# Schematic.net
KiCad netlist of a schematic drawn in EAGLE
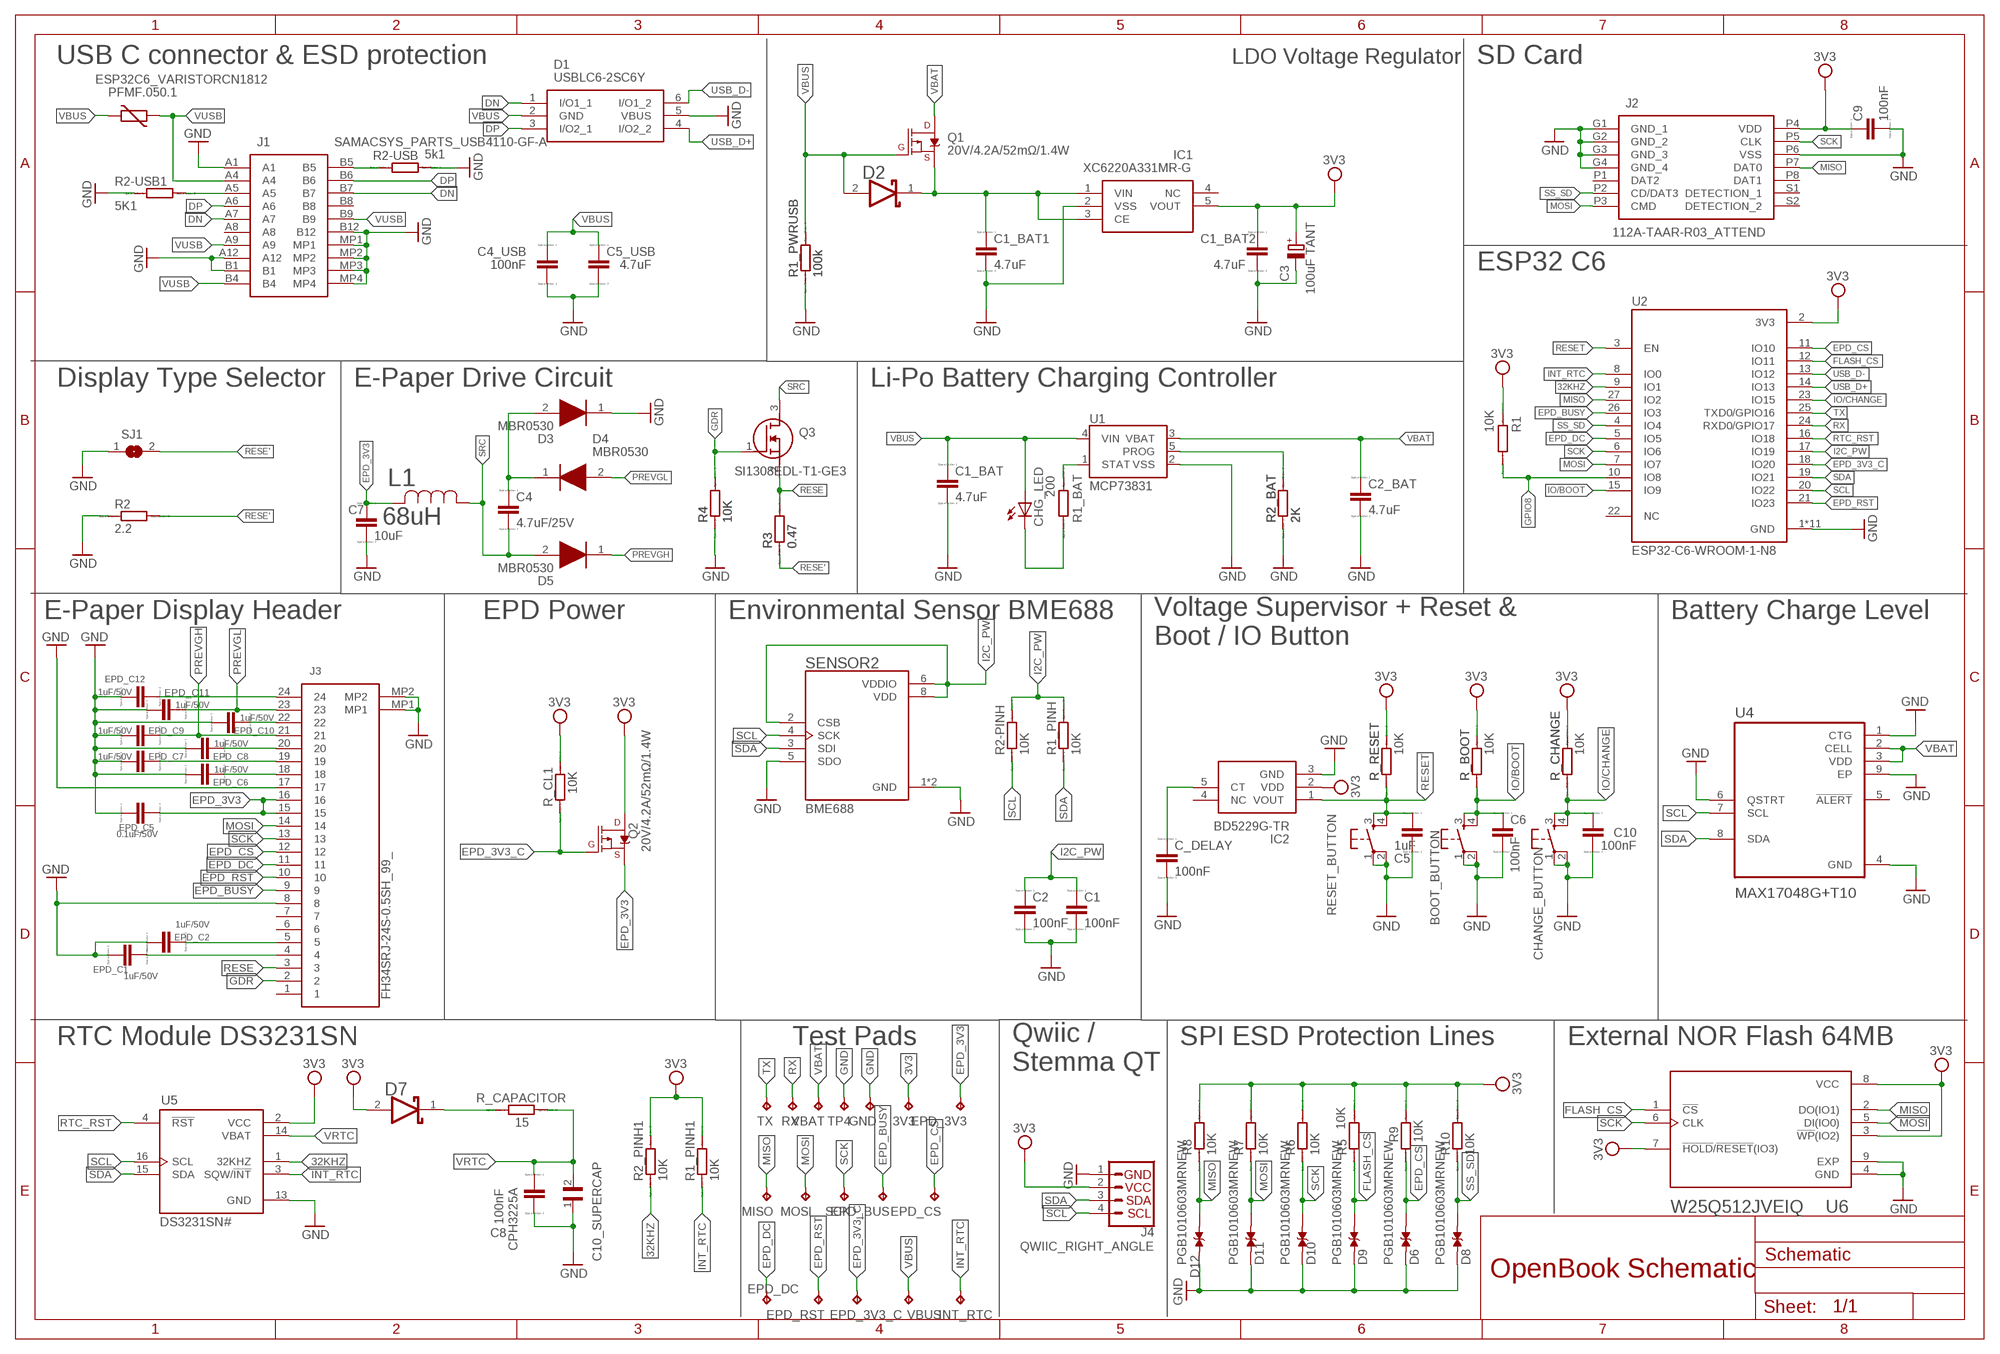
[diagram p0: schematic, sheet 1]

(export (version "E")
  (design (tool "Eeschema 10.0.6"))
  (components
    (comp (ref "3V3")
      (value "TP")
      (footprint "eagle-import:TP20R")
      (libsource (lib "eagle-import") (part "TP"))
    )
    (comp (ref "BOOT_BUTTON")
      (value "BUTTON_CUSYOMV1NEW")
      (footprint "eagle-import:MYBUTTON")
      (libsource (lib "eagle-import") (part "BUTTON_CUSYOMV1NEW"))
    )
    (comp (ref "C1")
      (value "100nF")
      (footprint "eagle-import:ESP32_WROVER_EAGLE-LTSPICE_C0402")
      (libsource (lib "eagle-import") (part "ESP32_WROVER_EAGLE-LTSPICE_C"))
    )
    (comp (ref "C1_BAT")
      (value "4.7uF")
      (footprint "eagle-import:ESP32_WROVER_EAGLE-LTSPICE_C0402")
      (libsource (lib "eagle-import") (part "ESP32_WROVER_EAGLE-LTSPICE_C"))
    )
    (comp (ref "C1_BAT1")
      (value "4.7uF")
      (footprint "eagle-import:ESP32_WROVER_EAGLE-LTSPICE_C0402")
      (libsource (lib "eagle-import") (part "ESP32_WROVER_EAGLE-LTSPICE_C"))
    )
    (comp (ref "C1_BAT2")
      (value "4.7uF")
      (footprint "eagle-import:ESP32_WROVER_EAGLE-LTSPICE_C0402")
      (libsource (lib "eagle-import") (part "ESP32_WROVER_EAGLE-LTSPICE_C"))
    )
    (comp (ref "C2")
      (value "100nF")
      (footprint "eagle-import:ESP32_WROVER_EAGLE-LTSPICE_C0402")
      (libsource (lib "eagle-import") (part "ESP32_WROVER_EAGLE-LTSPICE_C"))
    )
    (comp (ref "C2_BAT")
      (value "4.7uF")
      (footprint "eagle-import:ESP32_WROVER_EAGLE-LTSPICE_C0402")
      (libsource (lib "eagle-import") (part "ESP32_WROVER_EAGLE-LTSPICE_C"))
    )
    (comp (ref "C3")
      (value "100uF TANT")
      (footprint "eagle-import:RCL_CT3528")
      (libsource (lib "eagle-import") (part "RCL_CPOL-EUCT3528"))
    )
    (comp (ref "C4")
      (value "4.7uF/25V")
      (footprint "eagle-import:ESP32_WROVER_EAGLE-LTSPICE_C0402")
      (libsource (lib "eagle-import") (part "ESP32_WROVER_EAGLE-LTSPICE_C"))
    )
    (comp (ref "C4_USB")
      (value "100nF")
      (footprint "eagle-import:ESP32_WROVER_EAGLE-LTSPICE_C0402")
      (libsource (lib "eagle-import") (part "ESP32_WROVER_EAGLE-LTSPICE_C"))
    )
    (comp (ref "C5")
      (value "1uF")
      (footprint "eagle-import:ESP32_WROVER_EAGLE-LTSPICE_C0402")
      (libsource (lib "eagle-import") (part "ESP32_WROVER_EAGLE-LTSPICE_C"))
    )
    (comp (ref "C5_USB")
      (value "4.7uF")
      (footprint "eagle-import:ESP32_WROVER_EAGLE-LTSPICE_C0402")
      (libsource (lib "eagle-import") (part "ESP32_WROVER_EAGLE-LTSPICE_C"))
    )
    (comp (ref "C6")
      (value "100nF")
      (footprint "eagle-import:ESP32_WROVER_EAGLE-LTSPICE_C0402")
      (libsource (lib "eagle-import") (part "ESP32_WROVER_EAGLE-LTSPICE_C"))
    )
    (comp (ref "C7")
      (value "10uF")
      (footprint "eagle-import:ESP32_WROVER_EAGLE-LTSPICE_C0402")
      (libsource (lib "eagle-import") (part "ESP32_WROVER_EAGLE-LTSPICE_C"))
    )
    (comp (ref "C8")
      (value "100nF")
      (footprint "eagle-import:ESP32_WROVER_EAGLE-LTSPICE_C0402")
      (libsource (lib "eagle-import") (part "ESP32_WROVER_EAGLE-LTSPICE_C"))
    )
    (comp (ref "C9")
      (value "100nF")
      (footprint "eagle-import:ESP32_WROVER_EAGLE-LTSPICE_C0402")
      (libsource (lib "eagle-import") (part "ESP32_WROVER_EAGLE-LTSPICE_C"))
    )
    (comp (ref "C10")
      (value "100nF")
      (footprint "eagle-import:ESP32_WROVER_EAGLE-LTSPICE_C0402")
      (libsource (lib "eagle-import") (part "ESP32_WROVER_EAGLE-LTSPICE_C"))
    )
    (comp (ref "C10_SUPERCAP")
      (value "CPH3225A")
      (footprint "eagle-import:CAPCP3225X100N")
      (fields (field (name "MF") "Seiko Instruments"))
      (libsource (lib "eagle-import") (part "CPH3225A"))
    )
    (comp (ref "CHANGE_BUTTON")
      (value "BUTTON_CUSYOMV1NEW")
      (footprint "eagle-import:MYBUTTON")
      (libsource (lib "eagle-import") (part "BUTTON_CUSYOMV1NEW"))
    )
    (comp (ref "CHG_LED")
      (value "ADAFRUIT_LEDCHIP-LED0603")
      (footprint "eagle-import:ADAFRUIT_CHIP-LED0603")
      (libsource (lib "eagle-import") (part "ADAFRUIT_LEDCHIP-LED0603"))
    )
    (comp (ref "C_DELAY")
      (value "100nF")
      (footprint "eagle-import:ESP32_WROVER_EAGLE-LTSPICE_C0402")
      (libsource (lib "eagle-import") (part "ESP32_WROVER_EAGLE-LTSPICE_C"))
    )
    (comp (ref "D1")
      (value "USBLC6-2SC6Y")
      (footprint "eagle-import:SOT95P280X145-6N")
      (fields (field (name "MF") "STMicroelectronics"))
      (libsource (lib "eagle-import") (part "USBLC6-2SC6Y"))
    )
    (comp (ref "D2")
      (value "ESP32_WROVER_AVX---SD0805S020S1R0_AVX_SD0805S020S1R0_0_0AVX_SD0805S020S1R0_0_0")
      (footprint "eagle-import:ESP32_WROVER_AVX---SD0805S020S1R0_AVX_SD0805S020S1R0_0")
      (fields
        (field (name "DIGIKEY_PART_NUMBER") "478-7800-1-ND")
        (field (name "MF") "AVX")
        (field (name "MOUSER_PART_NUMBER") "581-SD0805S020S1R0")
      )
      (libsource (lib "eagle-import") (part "ESP32_WROVER_AVX---SD0805S020S1R0_AVX_SD0805S020S1R0_0_0AVX_SD0805S020S1R0_0_0"))
    )
    (comp (ref "D3")
      (value "MBR0530")
      (footprint "eagle-import:SOD3716X135N")
      (fields (field (name "MF") "ON Semiconductor"))
      (libsource (lib "eagle-import") (part "MBR0530"))
    )
    (comp (ref "D4")
      (value "MBR0530")
      (footprint "eagle-import:SOD3716X135N")
      (fields (field (name "MF") "ON Semiconductor"))
      (libsource (lib "eagle-import") (part "MBR0530"))
    )
    (comp (ref "D5")
      (value "MBR0530")
      (footprint "eagle-import:SOD3716X135N")
      (fields (field (name "MF") "ON Semiconductor"))
      (libsource (lib "eagle-import") (part "MBR0530"))
    )
    (comp (ref "D6")
      (value "PGB1010603MRNEW")
      (footprint "eagle-import:DIOC1608X36N")
      (libsource (lib "eagle-import") (part "PGB1010603MRNEW"))
    )
    (comp (ref "D7")
      (value "ESP32_WROVER_AVX---SD0805S020S1R0_AVX_SD0805S020S1R0_0_0AVX_SD0805S020S1R0_0_0")
      (footprint "eagle-import:ESP32_WROVER_AVX---SD0805S020S1R0_AVX_SD0805S020S1R0_0")
      (fields
        (field (name "DIGIKEY_PART_NUMBER") "478-7800-1-ND")
        (field (name "MF") "AVX")
        (field (name "MOUSER_PART_NUMBER") "581-SD0805S020S1R0")
      )
      (libsource (lib "eagle-import") (part "ESP32_WROVER_AVX---SD0805S020S1R0_AVX_SD0805S020S1R0_0_0AVX_SD0805S020S1R0_0_0"))
    )
    (comp (ref "D8")
      (value "PGB1010603MRNEW")
      (footprint "eagle-import:DIOC1608X36N")
      (libsource (lib "eagle-import") (part "PGB1010603MRNEW"))
    )
    (comp (ref "D9")
      (value "PGB1010603MRNEW")
      (footprint "eagle-import:DIOC1608X36N")
      (libsource (lib "eagle-import") (part "PGB1010603MRNEW"))
    )
    (comp (ref "D10")
      (value "PGB1010603MRNEW")
      (footprint "eagle-import:DIOC1608X36N")
      (libsource (lib "eagle-import") (part "PGB1010603MRNEW"))
    )
    (comp (ref "D11")
      (value "PGB1010603MRNEW")
      (footprint "eagle-import:DIOC1608X36N")
      (libsource (lib "eagle-import") (part "PGB1010603MRNEW"))
    )
    (comp (ref "D12")
      (value "PGB1010603MRNEW")
      (footprint "eagle-import:DIOC1608X36N")
      (libsource (lib "eagle-import") (part "PGB1010603MRNEW"))
    )
    (comp (ref "EPD_3V3")
      (value "TP")
      (footprint "eagle-import:TP20R")
      (libsource (lib "eagle-import") (part "TP"))
    )
    (comp (ref "EPD_3V3_C")
      (value "TP")
      (footprint "eagle-import:TP20R")
      (libsource (lib "eagle-import") (part "TP"))
    )
    (comp (ref "EPD_BUS")
      (value "TP")
      (footprint "eagle-import:TP20R")
      (libsource (lib "eagle-import") (part "TP"))
    )
    (comp (ref "EPD_C1")
      (value "1uF/50V")
      (footprint "eagle-import:ESP32_WROVER_EAGLE-LTSPICE_C0402")
      (libsource (lib "eagle-import") (part "ESP32_WROVER_EAGLE-LTSPICE_C"))
    )
    (comp (ref "EPD_C2")
      (value "1uF/50V")
      (footprint "eagle-import:ESP32_WROVER_EAGLE-LTSPICE_C0402")
      (libsource (lib "eagle-import") (part "ESP32_WROVER_EAGLE-LTSPICE_C"))
    )
    (comp (ref "EPD_C5")
      (value "0.1uF/50V")
      (footprint "eagle-import:ESP32_WROVER_EAGLE-LTSPICE_C0402")
      (libsource (lib "eagle-import") (part "ESP32_WROVER_EAGLE-LTSPICE_C"))
    )
    (comp (ref "EPD_C6")
      (value "1uF/50V")
      (footprint "eagle-import:ESP32_WROVER_EAGLE-LTSPICE_C0402")
      (libsource (lib "eagle-import") (part "ESP32_WROVER_EAGLE-LTSPICE_C"))
    )
    (comp (ref "EPD_C7")
      (value "1uF/50V")
      (footprint "eagle-import:ESP32_WROVER_EAGLE-LTSPICE_C0402")
      (libsource (lib "eagle-import") (part "ESP32_WROVER_EAGLE-LTSPICE_C"))
    )
    (comp (ref "EPD_C8")
      (value "1uF/50V")
      (footprint "eagle-import:ESP32_WROVER_EAGLE-LTSPICE_C0402")
      (libsource (lib "eagle-import") (part "ESP32_WROVER_EAGLE-LTSPICE_C"))
    )
    (comp (ref "EPD_C9")
      (value "1uF/50V")
      (footprint "eagle-import:ESP32_WROVER_EAGLE-LTSPICE_C0402")
      (libsource (lib "eagle-import") (part "ESP32_WROVER_EAGLE-LTSPICE_C"))
    )
    (comp (ref "EPD_C10")
      (value "1uF/50V")
      (footprint "eagle-import:ESP32_WROVER_EAGLE-LTSPICE_C0402")
      (libsource (lib "eagle-import") (part "ESP32_WROVER_EAGLE-LTSPICE_C"))
    )
    (comp (ref "EPD_C11")
      (value "1uF/50V")
      (footprint "eagle-import:ESP32_WROVER_EAGLE-LTSPICE_C0402")
      (libsource (lib "eagle-import") (part "ESP32_WROVER_EAGLE-LTSPICE_C"))
    )
    (comp (ref "EPD_C12")
      (value "1uF/50V")
      (footprint "eagle-import:ESP32_WROVER_EAGLE-LTSPICE_C0402")
      (libsource (lib "eagle-import") (part "ESP32_WROVER_EAGLE-LTSPICE_C"))
    )
    (comp (ref "EPD_CS")
      (value "TP")
      (footprint "eagle-import:TP20R")
      (libsource (lib "eagle-import") (part "TP"))
    )
    (comp (ref "EPD_DC")
      (value "TP")
      (footprint "eagle-import:TP20R")
      (libsource (lib "eagle-import") (part "TP"))
    )
    (comp (ref "EPD_RST")
      (value "TP")
      (footprint "eagle-import:TP20R")
      (libsource (lib "eagle-import") (part "TP"))
    )
    (comp (ref "GND")
      (value "TP")
      (footprint "eagle-import:TP20R")
      (libsource (lib "eagle-import") (part "TP"))
    )
    (comp (ref "IC1")
      (value "XC6220A331MR-G")
      (footprint "eagle-import:SOT95P280X120-5N")
      (fields (field (name "MOUSER_PART_NUMBER") "865-XC6220A331MR-G"))
      (libsource (lib "eagle-import") (part "XC6220A331MR-G"))
    )
    (comp (ref "IC2")
      (value "BD5229G-TR")
      (footprint "eagle-import:SOT95P280X125-5N")
      (fields (field (name "MOUSER_PART_NUMBER") "755-BD5229G-TR"))
      (libsource (lib "eagle-import") (part "BD5229G-TR"))
    )
    (comp (ref "INT_RTC")
      (value "TP")
      (footprint "eagle-import:TP20R")
      (libsource (lib "eagle-import") (part "TP"))
    )
    (comp (ref "J1")
      (value "SAMACSYS_PARTS_USB4110-GF-A")
      (footprint "eagle-import:SAMACSYS_PARTS_USB4110GFA")
      (fields
        (field (name "MANUFACTURER_PART_NUMBER") "USB4110-GF-A")
        (field (name "MOUSER_PART_NUMBER") "640-USB4110-GF-A")
      )
      (libsource (lib "eagle-import") (part "SAMACSYS_PARTS_USB4110-GF-A"))
    )
    (comp (ref "J2")
      (value "112A-TAAR-R03_ATTEND")
      (footprint "eagle-import:112ATAARR03ATTEND")
      (fields (field (name "MANUFACTURER_PART_NUMBER") "112A-TAAR-R03 ATTEND"))
      (libsource (lib "eagle-import") (part "112A-TAAR-R03_ATTEND"))
    )
    (comp (ref "J3")
      (value "FH34SRJ-24S-0.5SH_99_")
      (footprint "eagle-import:FH34SRJ24S05SH99")
      (fields
        (field (name "MANUFACTURER_PART_NUMBER") "FH34SRJ-24S-0.5SH(99)")
        (field (name "MOUSER_PART_NUMBER") "798-FH34SRJ24S05SH99")
      )
      (libsource (lib "eagle-import") (part "FH34SRJ-24S-0.5SH_99_"))
    )
    (comp (ref "J4")
      (value "QWIIC_RIGHT_ANGLE")
      (footprint "eagle-import:JST04_1MM_RA")
      (libsource (lib "eagle-import") (part "QWIIC_CONNECTORJS-1MM"))
    )
    (comp (ref "L1")
      (value "68uH")
      (footprint "eagle-import:IND_4828-WE-TPC_WRE")
      (fields
        (field (name "MANUFACTURER_PART_NUMBER") "744043680")
        (field (name "COPYRIGHT") "Copyright (C) 2024 Ultra Librarian. All rights reserved.")
      )
      (libsource (lib "eagle-import") (part "744043680IND_4828-WE-TPC_WRE"))
    )
    (comp (ref "MISO")
      (value "TP")
      (footprint "eagle-import:TP20R")
      (libsource (lib "eagle-import") (part "TP"))
    )
    (comp (ref "MOSI")
      (value "TP")
      (footprint "eagle-import:TP20R")
      (libsource (lib "eagle-import") (part "TP"))
    )
    (comp (ref "PFMF.050.1")
      (value "ESP32C6_VARISTORCN1812")
      (footprint "eagle-import:ESP32C6_VARISTOR_CT_CN1812")
      (libsource (lib "eagle-import") (part "ESP32C6_VARISTORCN1812"))
    )
    (comp (ref "Q1")
      (value "20V/4.2A/52mΩ/1.4W")
      (footprint "eagle-import:ESP32_WROVER_SPARKFUN-DISCRETESEMI_SOT23-3")
      (libsource (lib "eagle-import") (part "ESP32_WROVER_SPARKFUN-DISCRETESEMI_MOSFET_PCH-DMG2305UX-7"))
    )
    (comp (ref "Q2")
      (value "20V/4.2A/52mΩ/1.4W")
      (footprint "eagle-import:ESP32_WROVER_SPARKFUN-DISCRETESEMI_SOT23-3")
      (libsource (lib "eagle-import") (part "ESP32_WROVER_SPARKFUN-DISCRETESEMI_MOSFET_PCH-DMG2305UX-7"))
    )
    (comp (ref "Q3")
      (value "SI1308EDL-T1-GE3")
      (footprint "eagle-import:SOT65P210X110-3N")
      (fields (field (name "MF") "Vishay Siliconix"))
      (libsource (lib "eagle-import") (part "SI1308EDL-T1-GE3"))
    )
    (comp (ref "R1")
      (value "10K")
      (footprint "eagle-import:ESP32_WROVER_EAGLE-LTSPICE_R0402")
      (libsource (lib "eagle-import") (part "ESP32_WROVER_EAGLE-LTSPICE_R"))
    )
    (comp (ref "R1_BAT")
      (value "200")
      (footprint "eagle-import:ESP32_WROVER_EAGLE-LTSPICE_R0402")
      (libsource (lib "eagle-import") (part "ESP32_WROVER_EAGLE-LTSPICE_R"))
    )
    (comp (ref "R1_PINH")
      (value "10K")
      (footprint "eagle-import:ESP32_WROVER_EAGLE-LTSPICE_R0402")
      (libsource (lib "eagle-import") (part "ESP32_WROVER_EAGLE-LTSPICE_R"))
    )
    (comp (ref "R1_PINH1")
      (value "10K")
      (footprint "eagle-import:ESP32_WROVER_EAGLE-LTSPICE_R0402")
      (libsource (lib "eagle-import") (part "ESP32_WROVER_EAGLE-LTSPICE_R"))
    )
    (comp (ref "R1_PWRUSB")
      (value "100k")
      (footprint "eagle-import:ESP32_WROVER_EAGLE-LTSPICE_R0402")
      (libsource (lib "eagle-import") (part "ESP32_WROVER_EAGLE-LTSPICE_R"))
    )
    (comp (ref "R2")
      (value "2.2")
      (footprint "eagle-import:ESP32_WROVER_EAGLE-LTSPICE_R0402")
      (libsource (lib "eagle-import") (part "ESP32_WROVER_EAGLE-LTSPICE_R"))
    )
    (comp (ref "R2-PINH")
      (value "10K")
      (footprint "eagle-import:ESP32_WROVER_EAGLE-LTSPICE_R0402")
      (libsource (lib "eagle-import") (part "ESP32_WROVER_EAGLE-LTSPICE_R"))
    )
    (comp (ref "R2-USB")
      (value "5k1")
      (footprint "eagle-import:ESP32_WROVER_EAGLE-LTSPICE_R0402")
      (libsource (lib "eagle-import") (part "ESP32_WROVER_EAGLE-LTSPICE_R"))
    )
    (comp (ref "R2-USB1")
      (value "5K1")
      (footprint "eagle-import:ESP32_WROVER_EAGLE-LTSPICE_R0402")
      (libsource (lib "eagle-import") (part "ESP32_WROVER_EAGLE-LTSPICE_R"))
    )
    (comp (ref "R2_BAT")
      (value "2K")
      (footprint "eagle-import:ESP32_WROVER_EAGLE-LTSPICE_R0402")
      (libsource (lib "eagle-import") (part "ESP32_WROVER_EAGLE-LTSPICE_R"))
    )
    (comp (ref "R2_PINH1")
      (value "10K")
      (footprint "eagle-import:ESP32_WROVER_EAGLE-LTSPICE_R0402")
      (libsource (lib "eagle-import") (part "ESP32_WROVER_EAGLE-LTSPICE_R"))
    )
    (comp (ref "R3")
      (value "0.47")
      (footprint "eagle-import:ESP32_WROVER_EAGLE-LTSPICE_R0402")
      (libsource (lib "eagle-import") (part "ESP32_WROVER_EAGLE-LTSPICE_R"))
    )
    (comp (ref "R4")
      (value "10K")
      (footprint "eagle-import:ESP32_WROVER_EAGLE-LTSPICE_R0402")
      (libsource (lib "eagle-import") (part "ESP32_WROVER_EAGLE-LTSPICE_R"))
    )
    (comp (ref "R5")
      (value "10K")
      (footprint "eagle-import:ESP32_WROVER_EAGLE-LTSPICE_R0402")
      (libsource (lib "eagle-import") (part "ESP32_WROVER_EAGLE-LTSPICE_R"))
    )
    (comp (ref "R6")
      (value "10K")
      (footprint "eagle-import:ESP32_WROVER_EAGLE-LTSPICE_R0402")
      (libsource (lib "eagle-import") (part "ESP32_WROVER_EAGLE-LTSPICE_R"))
    )
    (comp (ref "R7")
      (value "10K")
      (footprint "eagle-import:ESP32_WROVER_EAGLE-LTSPICE_R0402")
      (libsource (lib "eagle-import") (part "ESP32_WROVER_EAGLE-LTSPICE_R"))
    )
    (comp (ref "R8")
      (value "10K")
      (footprint "eagle-import:ESP32_WROVER_EAGLE-LTSPICE_R0402")
      (libsource (lib "eagle-import") (part "ESP32_WROVER_EAGLE-LTSPICE_R"))
    )
    (comp (ref "R9")
      (value "10K")
      (footprint "eagle-import:ESP32_WROVER_EAGLE-LTSPICE_R0402")
      (libsource (lib "eagle-import") (part "ESP32_WROVER_EAGLE-LTSPICE_R"))
    )
    (comp (ref "R10")
      (value "10K")
      (footprint "eagle-import:ESP32_WROVER_EAGLE-LTSPICE_R0402")
      (libsource (lib "eagle-import") (part "ESP32_WROVER_EAGLE-LTSPICE_R"))
    )
    (comp (ref "RESET_BUTTON")
      (value "BUTTON_CUSYOMV1NEW")
      (footprint "eagle-import:MYBUTTON")
      (libsource (lib "eagle-import") (part "BUTTON_CUSYOMV1NEW"))
    )
    (comp (ref "RX")
      (value "TP")
      (footprint "eagle-import:TP20R")
      (libsource (lib "eagle-import") (part "TP"))
    )
    (comp (ref "R_BOOT")
      (value "10K")
      (footprint "eagle-import:ESP32_WROVER_EAGLE-LTSPICE_R0402")
      (libsource (lib "eagle-import") (part "ESP32_WROVER_EAGLE-LTSPICE_R"))
    )
    (comp (ref "R_CAPACITOR")
      (value "15")
      (footprint "eagle-import:ESP32_WROVER_EAGLE-LTSPICE_R0402")
      (libsource (lib "eagle-import") (part "ESP32_WROVER_EAGLE-LTSPICE_R"))
    )
    (comp (ref "R_CHANGE")
      (value "10K")
      (footprint "eagle-import:ESP32_WROVER_EAGLE-LTSPICE_R0402")
      (libsource (lib "eagle-import") (part "ESP32_WROVER_EAGLE-LTSPICE_R"))
    )
    (comp (ref "R_CL1")
      (value "10K")
      (footprint "eagle-import:ESP32_WROVER_EAGLE-LTSPICE_R0402")
      (libsource (lib "eagle-import") (part "ESP32_WROVER_EAGLE-LTSPICE_R"))
    )
    (comp (ref "R_RESET")
      (value "10K")
      (footprint "eagle-import:ESP32_WROVER_EAGLE-LTSPICE_R0402")
      (libsource (lib "eagle-import") (part "ESP32_WROVER_EAGLE-LTSPICE_R"))
    )
    (comp (ref "SCK")
      (value "TP")
      (footprint "eagle-import:TP20R")
      (libsource (lib "eagle-import") (part "TP"))
    )
    (comp (ref "SENSOR2")
      (value "ESP32_WROVER_BME680_BME680")
      (footprint "eagle-import:ESP32_WROVER_BME680_PSON80P300X300X100-8N")
      (fields (field (name "MF") "Bosch Sensortec") (field (name "MP") "BME680"))
      (libsource (lib "eagle-import") (part "ESP32_WROVER_BME680_BME680"))
    )
    (comp (ref "SJ1") (value "SJ") (footprint "eagle-import:SJ") (libsource (lib "eagle-import") (part "SJ")))
    (comp (ref "TP4")
      (value "TP")
      (footprint "eagle-import:TP20R")
      (libsource (lib "eagle-import") (part "TP"))
    )
    (comp (ref "TX")
      (value "TP")
      (footprint "eagle-import:TP20R")
      (libsource (lib "eagle-import") (part "TP"))
    )
    (comp (ref "U1")
      (value "ESP32_WROVER_SPARKFUN-IC-POWER_MCP73831")
      (footprint "eagle-import:ESP32_WROVER_SPARKFUN-IC-POWER_SOT23-5")
      (libsource (lib "eagle-import") (part "ESP32_WROVER_SPARKFUN-IC-POWER_MCP73831"))
    )
    (comp (ref "U2")
      (value "ESP32-C6-WROOM-1-N8")
      (footprint "eagle-import:XCVR_ESP32-C6-WROOM-1-N8")
      (fields (field (name "MF") "Espressif Systems"))
      (libsource (lib "eagle-import") (part "ESP32-C6-WROOM-1-N8"))
    )
    (comp (ref "U4")
      (value "MAX17048G+T10")
      (footprint "eagle-import:SON50P200X200X80-9N")
      (fields (field (name "MF") "Analog Devices"))
      (libsource (lib "eagle-import") (part "MAX17048G+T10"))
    )
    (comp (ref "U5")
      (value "DS3231SN#")
      (footprint "eagle-import:SOIC127P1032X265-16N")
      (fields (field (name "MF") "Analog Devices"))
      (libsource (lib "eagle-import") (part "DS3231SN#"))
    )
    (comp (ref "U6")
      (value "W25Q512JVEIQ")
      (footprint "eagle-import:SON127P600X800X80-9N")
      (fields (field (name "MF") "Winbond Electronics"))
      (libsource (lib "eagle-import") (part "W25Q512JVEIQ"))
    )
    (comp (ref "VBAT")
      (value "TP")
      (footprint "eagle-import:TP20R")
      (libsource (lib "eagle-import") (part "TP"))
    )
    (comp (ref "VBUS")
      (value "TP")
      (footprint "eagle-import:TP20R")
      (libsource (lib "eagle-import") (part "TP"))
    )
  )
  (nets
    (net (code "1") (name "3V3") (class "Default")
      (node (ref "3V3") (pin "TP") (pinfunction "TP_TP") (pintype "input"))
      (node (ref "C1_BAT2") (pin "1") (pinfunction "1_1") (pintype "passive"))
      (node (ref "C3") (pin "+") (pinfunction "+_+") (pintype "passive"))
      (node (ref "C9") (pin "1") (pinfunction "1_1") (pintype "passive"))
      (node (ref "D7") (pin "2") (pinfunction "ANODE_2") (pintype "bidirectional"))
      (node (ref "IC1") (pin "5") (pinfunction "VOUT_5") (pintype "bidirectional"))
      (node (ref "IC2") (pin "2") (pinfunction "VDD_2") (pintype "bidirectional"))
      (node (ref "J2") (pin "P4") (pinfunction "VDD_P4") (pintype "bidirectional"))
      (node (ref "J4") (pin "2") (pinfunction "2_2") (pintype "power_in"))
      (node (ref "Q2") (pin "3") (pinfunction "D_3") (pintype "bidirectional"))
      (node (ref "R1") (pin "2") (pinfunction "2_2") (pintype "passive"))
      (node (ref "R10") (pin "2") (pinfunction "2_2") (pintype "passive"))
      (node (ref "R1_PINH1") (pin "2") (pinfunction "2_2") (pintype "passive"))
      (node (ref "R2_PINH1") (pin "2") (pinfunction "2_2") (pintype "passive"))
      (node (ref "R5") (pin "2") (pinfunction "2_2") (pintype "passive"))
      (node (ref "R6") (pin "2") (pinfunction "2_2") (pintype "passive"))
      (node (ref "R7") (pin "2") (pinfunction "2_2") (pintype "passive"))
      (node (ref "R8") (pin "2") (pinfunction "2_2") (pintype "passive"))
      (node (ref "R9") (pin "2") (pinfunction "2_2") (pintype "passive"))
      (node (ref "R_BOOT") (pin "2") (pinfunction "2_2") (pintype "passive"))
      (node (ref "R_CHANGE") (pin "2") (pinfunction "2_2") (pintype "passive"))
      (node (ref "R_CL1") (pin "2") (pinfunction "2_2") (pintype "passive"))
      (node (ref "R_RESET") (pin "2") (pinfunction "2_2") (pintype "passive"))
      (node (ref "U2") (pin "2") (pinfunction "3V3_2") (pintype "power_in"))
      (node (ref "U5") (pin "2") (pinfunction "VCC_2") (pintype "power_in"))
      (node (ref "U6") (pin "3") (pinfunction "~{WP}(IO2)_3") (pintype "bidirectional"))
      (node (ref "U6") (pin "7") (pinfunction "~{HOLD}/~{RESET}(IO3)_7") (pintype "bidirectional"))
      (node (ref "U6") (pin "8") (pinfunction "VCC_8") (pintype "power_in"))
    )
    (net (code "2") (name "32KHZ") (class "Default")
      (node (ref "R2_PINH1") (pin "1") (pinfunction "1_1") (pintype "passive"))
      (node (ref "U2") (pin "9") (pinfunction "IO1_9") (pintype "bidirectional"))
      (node (ref "U5") (pin "1") (pinfunction "32KHZ_1") (pintype "output"))
    )
    (net (code "3") (name "DN") (class "Default")
      (node (ref "D1") (pin "1") (pinfunction "I/O1_1_1") (pintype "bidirectional"))
      (node (ref "J1") (pin "A7") (pinfunction "A7_A7") (pintype "bidirectional"))
      (node (ref "J1") (pin "B7") (pinfunction "B7_B7") (pintype "bidirectional"))
    )
    (net (code "4") (name "DP") (class "Default")
      (node (ref "D1") (pin "3") (pinfunction "I/O2_1_3") (pintype "bidirectional"))
      (node (ref "J1") (pin "A6") (pinfunction "A6_A6") (pintype "bidirectional"))
      (node (ref "J1") (pin "B6") (pinfunction "B6_B6") (pintype "bidirectional"))
    )
    (net (code "5") (name "EPD_3V3") (class "Default")
      (node (ref "C7") (pin "1") (pinfunction "1_1") (pintype "passive"))
      (node (ref "EPD_3V3") (pin "TP") (pinfunction "TP_TP") (pintype "input"))
      (node (ref "EPD_C5") (pin "2") (pinfunction "2_2") (pintype "passive"))
      (node (ref "J3") (pin "15") (pinfunction "15_15") (pintype "bidirectional"))
      (node (ref "J3") (pin "16") (pinfunction "16_16") (pintype "bidirectional"))
      (node (ref "L1") (pin "2") (pinfunction "2_2") (pintype "passive"))
      (node (ref "Q2") (pin "2") (pinfunction "S_2") (pintype "bidirectional"))
    )
    (net (code "6") (name "EPD_3V3_C") (class "Default")
      (node (ref "EPD_3V3_C") (pin "TP") (pinfunction "TP_TP") (pintype "input"))
      (node (ref "Q2") (pin "1") (pinfunction "G_1") (pintype "bidirectional"))
      (node (ref "R_CL1") (pin "1") (pinfunction "1_1") (pintype "passive"))
      (node (ref "U2") (pin "18") (pinfunction "IO20_18") (pintype "bidirectional"))
    )
    (net (code "7") (name "EPD_BUSY") (class "Default")
      (node (ref "EPD_BUS") (pin "TP") (pinfunction "TP_TP") (pintype "input"))
      (node (ref "J3") (pin "9") (pinfunction "9_9") (pintype "bidirectional"))
      (node (ref "U2") (pin "26") (pinfunction "IO3_26") (pintype "bidirectional"))
    )
    (net (code "8") (name "EPD_CS") (class "Default")
      (node (ref "D6") (pin "1") (pinfunction "2_1") (pintype "passive"))
      (node (ref "EPD_CS") (pin "TP") (pinfunction "TP_TP") (pintype "input"))
      (node (ref "J3") (pin "12") (pinfunction "12_12") (pintype "bidirectional"))
      (node (ref "R9") (pin "1") (pinfunction "1_1") (pintype "passive"))
      (node (ref "U2") (pin "11") (pinfunction "IO10_11") (pintype "bidirectional"))
    )
    (net (code "9") (name "EPD_DC") (class "Default")
      (node (ref "EPD_DC") (pin "TP") (pinfunction "TP_TP") (pintype "input"))
      (node (ref "J3") (pin "11") (pinfunction "11_11") (pintype "bidirectional"))
      (node (ref "U2") (pin "5") (pinfunction "IO5_5") (pintype "bidirectional"))
    )
    (net (code "10") (name "EPD_RST") (class "Default")
      (node (ref "EPD_RST") (pin "TP") (pinfunction "TP_TP") (pintype "input"))
      (node (ref "J3") (pin "10") (pinfunction "10_10") (pintype "bidirectional"))
      (node (ref "U2") (pin "21") (pinfunction "IO23_21") (pintype "bidirectional"))
    )
    (net (code "11") (name "FLASH_CS") (class "Default")
      (node (ref "D9") (pin "1") (pinfunction "2_1") (pintype "passive"))
      (node (ref "R5") (pin "1") (pinfunction "1_1") (pintype "passive"))
      (node (ref "U2") (pin "12") (pinfunction "IO11_12") (pintype "bidirectional"))
      (node (ref "U6") (pin "1") (pinfunction "~{CS}_1") (pintype "input"))
    )
    (net (code "12") (name "GDR") (class "Default")
      (node (ref "J3") (pin "2") (pinfunction "2_2") (pintype "bidirectional"))
      (node (ref "Q3") (pin "1") (pinfunction "G_1") (pintype "bidirectional"))
      (node (ref "R4") (pin "2") (pinfunction "2_2") (pintype "passive"))
    )
    (net (code "13") (name "GND") (class "Default")
      (node (ref "BOOT_BUTTON") (pin "1") (pinfunction "1_1") (pintype "passive"))
      (node (ref "BOOT_BUTTON") (pin "2") (pinfunction "2_2") (pintype "passive"))
      (node (ref "C1") (pin "2") (pinfunction "2_2") (pintype "passive"))
      (node (ref "C10") (pin "2") (pinfunction "2_2") (pintype "passive"))
      (node (ref "C10_SUPERCAP") (pin "1") (pinfunction "1_1") (pintype "passive"))
      (node (ref "C1_BAT") (pin "2") (pinfunction "2_2") (pintype "passive"))
      (node (ref "C1_BAT1") (pin "2") (pinfunction "2_2") (pintype "passive"))
      (node (ref "C1_BAT2") (pin "2") (pinfunction "2_2") (pintype "passive"))
      (node (ref "C2") (pin "2") (pinfunction "2_2") (pintype "passive"))
      (node (ref "C2_BAT") (pin "2") (pinfunction "2_2") (pintype "passive"))
      (node (ref "C3") (pin "-") (pinfunction "-_-") (pintype "passive"))
      (node (ref "C4_USB") (pin "2") (pinfunction "2_2") (pintype "passive"))
      (node (ref "C5") (pin "2") (pinfunction "2_2") (pintype "passive"))
      (node (ref "C5_USB") (pin "2") (pinfunction "2_2") (pintype "passive"))
      (node (ref "C6") (pin "2") (pinfunction "2_2") (pintype "passive"))
      (node (ref "C7") (pin "2") (pinfunction "2_2") (pintype "passive"))
      (node (ref "C8") (pin "2") (pinfunction "2_2") (pintype "passive"))
      (node (ref "C9") (pin "2") (pinfunction "2_2") (pintype "passive"))
      (node (ref "CHANGE_BUTTON") (pin "1") (pinfunction "1_1") (pintype "passive"))
      (node (ref "CHANGE_BUTTON") (pin "2") (pinfunction "2_2") (pintype "passive"))
      (node (ref "C_DELAY") (pin "2") (pinfunction "2_2") (pintype "passive"))
      (node (ref "D1") (pin "5") (pinfunction "VBUS_5") (pintype "bidirectional"))
      (node (ref "D10") (pin "2") (pinfunction "1_2") (pintype "passive"))
      (node (ref "D11") (pin "2") (pinfunction "1_2") (pintype "passive"))
      (node (ref "D12") (pin "2") (pinfunction "1_2") (pintype "passive"))
      (node (ref "D3") (pin "1") (pinfunction "K_1") (pintype "bidirectional"))
      (node (ref "D6") (pin "2") (pinfunction "1_2") (pintype "passive"))
      (node (ref "D8") (pin "2") (pinfunction "1_2") (pintype "passive"))
      (node (ref "D9") (pin "2") (pinfunction "1_2") (pintype "passive"))
      (node (ref "EPD_C1") (pin "1") (pinfunction "1_1") (pintype "passive"))
      (node (ref "EPD_C10") (pin "1") (pinfunction "1_1") (pintype "passive"))
      (node (ref "EPD_C11") (pin "1") (pinfunction "1_1") (pintype "passive"))
      (node (ref "EPD_C12") (pin "1") (pinfunction "1_1") (pintype "passive"))
      (node (ref "EPD_C2") (pin "1") (pinfunction "1_1") (pintype "passive"))
      (node (ref "EPD_C5") (pin "1") (pinfunction "1_1") (pintype "passive"))
      (node (ref "EPD_C6") (pin "1") (pinfunction "1_1") (pintype "passive"))
      (node (ref "EPD_C7") (pin "1") (pinfunction "1_1") (pintype "passive"))
      (node (ref "EPD_C8") (pin "1") (pinfunction "1_1") (pintype "passive"))
      (node (ref "EPD_C9") (pin "1") (pinfunction "1_1") (pintype "passive"))
      (node (ref "GND") (pin "TP") (pinfunction "TP_TP") (pintype "input"))
      (node (ref "IC1") (pin "2") (pinfunction "VSS_2") (pintype "bidirectional"))
      (node (ref "IC2") (pin "3") (pinfunction "GND_3") (pintype "bidirectional"))
      (node (ref "J1") (pin "A1") (pinfunction "A1_A1") (pintype "bidirectional"))
      (node (ref "J1") (pin "A12") (pinfunction "A12_A12") (pintype "bidirectional"))
      (node (ref "J1") (pin "B1") (pinfunction "B1_B1") (pintype "bidirectional"))
      (node (ref "J1") (pin "B12") (pinfunction "B12_B12") (pintype "bidirectional"))
      (node (ref "J1") (pin "MP1") (pinfunction "MP1_MP1") (pintype "bidirectional"))
      (node (ref "J1") (pin "MP2") (pinfunction "MP2_MP2") (pintype "bidirectional"))
      (node (ref "J1") (pin "MP3") (pinfunction "MP3_MP3") (pintype "bidirectional"))
      (node (ref "J1") (pin "MP4") (pinfunction "MP4_MP4") (pintype "bidirectional"))
      (node (ref "J2") (pin "G1") (pinfunction "GND_1_G1") (pintype "bidirectional"))
      (node (ref "J2") (pin "G2") (pinfunction "GND_2_G2") (pintype "bidirectional"))
      (node (ref "J2") (pin "G3") (pinfunction "GND_3_G3") (pintype "bidirectional"))
      (node (ref "J2") (pin "G4") (pinfunction "GND_4_G4") (pintype "bidirectional"))
      (node (ref "J2") (pin "P6") (pinfunction "VSS_P6") (pintype "bidirectional"))
      (node (ref "J3") (pin "17") (pinfunction "17_17") (pintype "bidirectional"))
      (node (ref "J3") (pin "8") (pinfunction "8_8") (pintype "bidirectional"))
      (node (ref "J3") (pin "MP1") (pinfunction "MP1_MP1") (pintype "bidirectional"))
      (node (ref "J3") (pin "MP2") (pinfunction "MP2_MP2") (pintype "bidirectional"))
      (node (ref "J4") (pin "1") (pinfunction "1_1") (pintype "power_in"))
      (node (ref "R1_PWRUSB") (pin "1") (pinfunction "1_1") (pintype "passive"))
      (node (ref "R2") (pin "1") (pinfunction "1_1") (pintype "passive"))
      (node (ref "R2-USB") (pin "2") (pinfunction "2_2") (pintype "passive"))
      (node (ref "R2-USB1") (pin "1") (pinfunction "1_1") (pintype "passive"))
      (node (ref "R2_BAT") (pin "1") (pinfunction "1_1") (pintype "passive"))
      (node (ref "R4") (pin "1") (pinfunction "1_1") (pintype "passive"))
      (node (ref "RESET_BUTTON") (pin "1") (pinfunction "1_1") (pintype "passive"))
      (node (ref "RESET_BUTTON") (pin "2") (pinfunction "2_2") (pintype "passive"))
      (node (ref "SENSOR2") (pin "1") (pinfunction "GND_1") (pintype "power_in"))
      (node (ref "SENSOR2") (pin "5") (pinfunction "SDO_5") (pintype "bidirectional"))
      (node (ref "SENSOR2") (pin "7") (pinfunction "GND_7") (pintype "power_in"))
      (node (ref "SJ1") (pin "1") (pinfunction "1_1") (pintype "passive"))
      (node (ref "TP4") (pin "TP") (pinfunction "TP_TP") (pintype "input"))
      (node (ref "U1") (pin "2") (pinfunction "VSS_2") (pintype "power_in"))
      (node (ref "U2") (pin "1") (pinfunction "GND_1") (pintype "power_in"))
      (node (ref "U2") (pin "28") (pinfunction "GND_28") (pintype "power_in"))
      (node (ref "U2") (pin "29_1") (pinfunction "GND_29_1") (pintype "power_in"))
      (node (ref "U2") (pin "29_2") (pinfunction "GND_29_2") (pintype "power_in"))
      (node (ref "U2") (pin "29_3") (pinfunction "GND_29_3") (pintype "power_in"))
      (node (ref "U2") (pin "29_4") (pinfunction "GND_29_4") (pintype "power_in"))
      (node (ref "U2") (pin "29_5") (pinfunction "GND_29_5") (pintype "power_in"))
      (node (ref "U2") (pin "29_6") (pinfunction "GND_29_6") (pintype "power_in"))
      (node (ref "U2") (pin "29_7") (pinfunction "GND_29_7") (pintype "power_in"))
      (node (ref "U2") (pin "29_8") (pinfunction "GND_29_8") (pintype "power_in"))
      (node (ref "U2") (pin "29_9") (pinfunction "GND_29_9") (pintype "power_in"))
      (node (ref "U4") (pin "1") (pinfunction "CTG_1") (pintype "power_in"))
      (node (ref "U4") (pin "4") (pinfunction "GND_4") (pintype "power_in"))
      (node (ref "U4") (pin "6") (pinfunction "QSTRT_6") (pintype "input"))
      (node (ref "U4") (pin "9") (pinfunction "EP_9") (pintype "power_in"))
      (node (ref "U5") (pin "13") (pinfunction "GND_13") (pintype "power_in"))
      (node (ref "U6") (pin "4") (pinfunction "GND_4") (pintype "power_in"))
      (node (ref "U6") (pin "9") (pinfunction "EXP_9") (pintype "passive"))
    )
    (net (code "14") (name "GPIO8") (class "Default")
      (node (ref "R1") (pin "1") (pinfunction "1_1") (pintype "passive"))
      (node (ref "U2") (pin "10") (pinfunction "IO8_10") (pintype "bidirectional"))
    )
    (net (code "15") (name "I2C_PW") (class "Default")
      (node (ref "C1") (pin "1") (pinfunction "1_1") (pintype "passive"))
      (node (ref "C2") (pin "1") (pinfunction "1_1") (pintype "passive"))
      (node (ref "R1_PINH") (pin "2") (pinfunction "2_2") (pintype "passive"))
      (node (ref "R2-PINH") (pin "2") (pinfunction "2_2") (pintype "passive"))
      (node (ref "SENSOR2") (pin "2") (pinfunction "CSB_2") (pintype "input"))
      (node (ref "SENSOR2") (pin "6") (pinfunction "VDDIO_6") (pintype "power_in"))
      (node (ref "SENSOR2") (pin "8") (pinfunction "VDD_8") (pintype "power_in"))
      (node (ref "U2") (pin "17") (pinfunction "IO19_17") (pintype "bidirectional"))
    )
    (net (code "16") (name "INT_RTC") (class "Default")
      (node (ref "INT_RTC") (pin "TP") (pinfunction "TP_TP") (pintype "input"))
      (node (ref "R1_PINH1") (pin "1") (pinfunction "1_1") (pintype "passive"))
      (node (ref "U2") (pin "8") (pinfunction "IO0_8") (pintype "bidirectional"))
      (node (ref "U5") (pin "3") (pinfunction "SQW/~{INT}_3") (pintype "output"))
    )
    (net (code "17") (name "IO{slash}BOOT") (class "Default")
      (node (ref "BOOT_BUTTON") (pin "3") (pinfunction "3_3") (pintype "passive"))
      (node (ref "BOOT_BUTTON") (pin "4") (pinfunction "4_4") (pintype "passive"))
      (node (ref "C6") (pin "1") (pinfunction "1_1") (pintype "passive"))
      (node (ref "R_BOOT") (pin "1") (pinfunction "1_1") (pintype "passive"))
      (node (ref "U2") (pin "15") (pinfunction "IO9_15") (pintype "bidirectional"))
    )
    (net (code "18") (name "IO{slash}CHANGE") (class "Default")
      (node (ref "C10") (pin "1") (pinfunction "1_1") (pintype "passive"))
      (node (ref "CHANGE_BUTTON") (pin "3") (pinfunction "3_3") (pintype "passive"))
      (node (ref "CHANGE_BUTTON") (pin "4") (pinfunction "4_4") (pintype "passive"))
      (node (ref "R_CHANGE") (pin "1") (pinfunction "1_1") (pintype "passive"))
      (node (ref "U2") (pin "23") (pinfunction "IO15_23") (pintype "bidirectional"))
    )
    (net (code "19") (name "MISO") (class "Default")
      (node (ref "D12") (pin "1") (pinfunction "2_1") (pintype "passive"))
      (node (ref "J2") (pin "P7") (pinfunction "DAT0_P7") (pintype "bidirectional"))
      (node (ref "MISO") (pin "TP") (pinfunction "TP_TP") (pintype "input"))
      (node (ref "R8") (pin "1") (pinfunction "1_1") (pintype "passive"))
      (node (ref "U2") (pin "27") (pinfunction "IO2_27") (pintype "bidirectional"))
      (node (ref "U6") (pin "2") (pinfunction "DO(IO1)_2") (pintype "bidirectional"))
    )
    (net (code "20") (name "MOSI") (class "Default")
      (node (ref "D11") (pin "1") (pinfunction "2_1") (pintype "passive"))
      (node (ref "J2") (pin "P3") (pinfunction "CMD_P3") (pintype "bidirectional"))
      (node (ref "J3") (pin "14") (pinfunction "14_14") (pintype "bidirectional"))
      (node (ref "MOSI") (pin "TP") (pinfunction "TP_TP") (pintype "input"))
      (node (ref "R7") (pin "1") (pinfunction "1_1") (pintype "passive"))
      (node (ref "U2") (pin "7") (pinfunction "IO7_7") (pintype "bidirectional"))
      (node (ref "U6") (pin "5") (pinfunction "DI(IO0)_5") (pintype "bidirectional"))
    )
    (net (code "21") (name "Net-(CHG_LED-PadC)") (class "Default")
      (node (ref "CHG_LED") (pin "C") (pinfunction "C_C") (pintype "passive"))
      (node (ref "R1_BAT") (pin "1") (pinfunction "1_1") (pintype "passive"))
    )
    (net (code "22") (name "Net-(D2-CATHODE)") (class "Default")
      (node (ref "C1_BAT1") (pin "1") (pinfunction "1_1") (pintype "passive"))
      (node (ref "D2") (pin "1") (pinfunction "CATHODE_1") (pintype "bidirectional"))
      (node (ref "IC1") (pin "1") (pinfunction "VIN_1") (pintype "bidirectional"))
      (node (ref "IC1") (pin "3") (pinfunction "CE_3") (pintype "bidirectional"))
      (node (ref "Q1") (pin "2") (pinfunction "S_2") (pintype "bidirectional"))
    )
    (net (code "23") (name "Net-(D3-A)") (class "Default")
      (node (ref "C4") (pin "1") (pinfunction "1_1") (pintype "passive"))
      (node (ref "D3") (pin "2") (pinfunction "A_2") (pintype "bidirectional"))
      (node (ref "D4") (pin "1") (pinfunction "K_1") (pintype "bidirectional"))
    )
    (net (code "24") (name "Net-(D7-CATHODE)") (class "Default")
      (node (ref "D7") (pin "1") (pinfunction "CATHODE_1") (pintype "bidirectional"))
      (node (ref "R_CAPACITOR") (pin "1") (pinfunction "1_1") (pintype "passive"))
    )
    (net (code "25") (name "Net-(EPD_C1-Pad2)") (class "Default")
      (node (ref "EPD_C1") (pin "2") (pinfunction "2_2") (pintype "passive"))
      (node (ref "J3") (pin "4") (pinfunction "4_4") (pintype "bidirectional"))
    )
    (net (code "26") (name "Net-(EPD_C2-Pad2)") (class "Default")
      (node (ref "EPD_C2") (pin "2") (pinfunction "2_2") (pintype "passive"))
      (node (ref "J3") (pin "5") (pinfunction "5_5") (pintype "bidirectional"))
    )
    (net (code "27") (name "Net-(EPD_C6-Pad2)") (class "Default")
      (node (ref "EPD_C6") (pin "2") (pinfunction "2_2") (pintype "passive"))
      (node (ref "J3") (pin "18") (pinfunction "18_18") (pintype "bidirectional"))
    )
    (net (code "28") (name "Net-(EPD_C7-Pad2)") (class "Default")
      (node (ref "EPD_C7") (pin "2") (pinfunction "2_2") (pintype "passive"))
      (node (ref "J3") (pin "19") (pinfunction "19_19") (pintype "bidirectional"))
    )
    (net (code "29") (name "Net-(EPD_C8-Pad2)") (class "Default")
      (node (ref "EPD_C8") (pin "2") (pinfunction "2_2") (pintype "passive"))
      (node (ref "J3") (pin "20") (pinfunction "20_20") (pintype "bidirectional"))
    )
    (net (code "30") (name "Net-(EPD_C10-Pad2)") (class "Default")
      (node (ref "EPD_C10") (pin "2") (pinfunction "2_2") (pintype "passive"))
      (node (ref "J3") (pin "22") (pinfunction "22_22") (pintype "bidirectional"))
    )
    (net (code "31") (name "Net-(EPD_C12-Pad2)") (class "Default")
      (node (ref "EPD_C12") (pin "2") (pinfunction "2_2") (pintype "passive"))
      (node (ref "J3") (pin "24") (pinfunction "24_24") (pintype "bidirectional"))
    )
    (net (code "32") (name "Net-(IC2-CT)") (class "Default")
      (node (ref "C_DELAY") (pin "1") (pinfunction "1_1") (pintype "passive"))
      (node (ref "IC2") (pin "5") (pinfunction "CT_5") (pintype "bidirectional"))
    )
    (net (code "33") (name "Net-(J1-PadA5)") (class "Default")
      (node (ref "J1") (pin "A5") (pinfunction "A5_A5") (pintype "bidirectional"))
      (node (ref "R2-USB1") (pin "2") (pinfunction "2_2") (pintype "passive"))
    )
    (net (code "34") (name "Net-(J1-PadB5)") (class "Default")
      (node (ref "J1") (pin "B5") (pinfunction "B5_B5") (pintype "bidirectional"))
      (node (ref "R2-USB") (pin "1") (pinfunction "1_1") (pintype "passive"))
    )
    (net (code "35") (name "Net-(U1-PROG)") (class "Default")
      (node (ref "R2_BAT") (pin "2") (pinfunction "2_2") (pintype "passive"))
      (node (ref "U1") (pin "5") (pinfunction "PROG_5") (pintype "input"))
    )
    (net (code "36") (name "Net-(U1-STAT)") (class "Default")
      (node (ref "R1_BAT") (pin "2") (pinfunction "2_2") (pintype "passive"))
      (node (ref "U1") (pin "1") (pinfunction "STAT_1") (pintype "output"))
    )
    (net (code "37") (name "PREVGH") (class "Default")
      (node (ref "D5") (pin "1") (pinfunction "K_1") (pintype "bidirectional"))
      (node (ref "EPD_C9") (pin "2") (pinfunction "2_2") (pintype "passive"))
      (node (ref "J3") (pin "21") (pinfunction "21_21") (pintype "bidirectional"))
    )
    (net (code "38") (name "PREVGL") (class "Default")
      (node (ref "D4") (pin "2") (pinfunction "A_2") (pintype "bidirectional"))
      (node (ref "EPD_C11") (pin "2") (pinfunction "2_2") (pintype "passive"))
      (node (ref "J3") (pin "23") (pinfunction "23_23") (pintype "bidirectional"))
    )
    (net (code "39") (name "RESE") (class "Default")
      (node (ref "J3") (pin "3") (pinfunction "3_3") (pintype "bidirectional"))
      (node (ref "Q3") (pin "2") (pinfunction "S_2") (pintype "bidirectional"))
      (node (ref "R3") (pin "2") (pinfunction "2_2") (pintype "passive"))
    )
    (net (code "40") (name "RESE'") (class "Default")
      (node (ref "R2") (pin "2") (pinfunction "2_2") (pintype "passive"))
      (node (ref "R3") (pin "1") (pinfunction "1_1") (pintype "passive"))
      (node (ref "SJ1") (pin "2") (pinfunction "2_2") (pintype "passive"))
    )
    (net (code "41") (name "RESET") (class "Default")
      (node (ref "C5") (pin "1") (pinfunction "1_1") (pintype "passive"))
      (node (ref "IC2") (pin "1") (pinfunction "VOUT_1") (pintype "bidirectional"))
      (node (ref "RESET_BUTTON") (pin "3") (pinfunction "3_3") (pintype "passive"))
      (node (ref "RESET_BUTTON") (pin "4") (pinfunction "4_4") (pintype "passive"))
      (node (ref "R_RESET") (pin "1") (pinfunction "1_1") (pintype "passive"))
      (node (ref "U2") (pin "3") (pinfunction "EN_3") (pintype "input"))
    )
    (net (code "42") (name "RTC_RST") (class "Default")
      (node (ref "U2") (pin "16") (pinfunction "IO18_16") (pintype "bidirectional"))
      (node (ref "U5") (pin "4") (pinfunction "~{RST}_4") (pintype "input"))
    )
    (net (code "43") (name "RX") (class "Default")
      (node (ref "RX") (pin "TP") (pinfunction "TP_TP") (pintype "input"))
      (node (ref "U2") (pin "24") (pinfunction "RXD0/GPIO17_24") (pintype "bidirectional"))
    )
    (net (code "44") (name "SCK") (class "Default")
      (node (ref "D10") (pin "1") (pinfunction "2_1") (pintype "passive"))
      (node (ref "J2") (pin "P5") (pinfunction "CLK_P5") (pintype "bidirectional"))
      (node (ref "J3") (pin "13") (pinfunction "13_13") (pintype "bidirectional"))
      (node (ref "R6") (pin "1") (pinfunction "1_1") (pintype "passive"))
      (node (ref "SCK") (pin "TP") (pinfunction "TP_TP") (pintype "input"))
      (node (ref "U2") (pin "6") (pinfunction "IO6_6") (pintype "bidirectional"))
      (node (ref "U6") (pin "6") (pinfunction "CLK_6") (pintype "input"))
    )
    (net (code "45") (name "SCL") (class "Default")
      (node (ref "J4") (pin "4") (pinfunction "4_4") (pintype "passive"))
      (node (ref "R2-PINH") (pin "1") (pinfunction "1_1") (pintype "passive"))
      (node (ref "SENSOR2") (pin "4") (pinfunction "SCK_4") (pintype "input"))
      (node (ref "U2") (pin "20") (pinfunction "IO22_20") (pintype "bidirectional"))
      (node (ref "U4") (pin "7") (pinfunction "SCL_7") (pintype "input"))
      (node (ref "U5") (pin "16") (pinfunction "SCL_16") (pintype "input"))
    )
    (net (code "46") (name "SDA") (class "Default")
      (node (ref "J4") (pin "3") (pinfunction "3_3") (pintype "passive"))
      (node (ref "R1_PINH") (pin "1") (pinfunction "1_1") (pintype "passive"))
      (node (ref "SENSOR2") (pin "3") (pinfunction "SDI_3") (pintype "bidirectional"))
      (node (ref "U2") (pin "19") (pinfunction "IO21_19") (pintype "bidirectional"))
      (node (ref "U4") (pin "8") (pinfunction "SDA_8") (pintype "bidirectional"))
      (node (ref "U5") (pin "15") (pinfunction "SDA_15") (pintype "bidirectional"))
    )
    (net (code "47") (name "SRC") (class "Default")
      (node (ref "C4") (pin "2") (pinfunction "2_2") (pintype "passive"))
      (node (ref "D5") (pin "2") (pinfunction "A_2") (pintype "bidirectional"))
      (node (ref "L1") (pin "1") (pinfunction "1_1") (pintype "passive"))
      (node (ref "Q3") (pin "3") (pinfunction "D_3") (pintype "bidirectional"))
    )
    (net (code "48") (name "SS_SD") (class "Default")
      (node (ref "D8") (pin "1") (pinfunction "2_1") (pintype "passive"))
      (node (ref "J2") (pin "P2") (pinfunction "CD/DAT3_P2") (pintype "bidirectional"))
      (node (ref "R10") (pin "1") (pinfunction "1_1") (pintype "passive"))
      (node (ref "U2") (pin "4") (pinfunction "IO4_4") (pintype "bidirectional"))
    )
    (net (code "49") (name "TX") (class "Default")
      (node (ref "TX") (pin "TP") (pinfunction "TP_TP") (pintype "input"))
      (node (ref "U2") (pin "25") (pinfunction "TXD0/GPIO16_25") (pintype "bidirectional"))
    )
    (net (code "50") (name "USB_D+") (class "Default")
      (node (ref "D1") (pin "4") (pinfunction "I/O2_2_4") (pintype "bidirectional"))
      (node (ref "U2") (pin "14") (pinfunction "IO13_14") (pintype "bidirectional"))
    )
    (net (code "51") (name "USB_D-") (class "Default")
      (node (ref "D1") (pin "6") (pinfunction "I/O1_2_6") (pintype "bidirectional"))
      (node (ref "U2") (pin "13") (pinfunction "IO12_13") (pintype "bidirectional"))
    )
    (net (code "52") (name "VBAT") (class "Default")
      (node (ref "C2_BAT") (pin "1") (pinfunction "1_1") (pintype "passive"))
      (node (ref "Q1") (pin "3") (pinfunction "D_3") (pintype "bidirectional"))
      (node (ref "U1") (pin "3") (pinfunction "VBAT_3") (pintype "power_in"))
      (node (ref "U4") (pin "2") (pinfunction "CELL_2") (pintype "power_in"))
      (node (ref "U4") (pin "3") (pinfunction "VDD_3") (pintype "power_in"))
      (node (ref "VBAT") (pin "TP") (pinfunction "TP_TP") (pintype "input"))
    )
    (net (code "53") (name "VBUS") (class "Default")
      (node (ref "C1_BAT") (pin "1") (pinfunction "1_1") (pintype "passive"))
      (node (ref "C4_USB") (pin "1") (pinfunction "1_1") (pintype "passive"))
      (node (ref "C5_USB") (pin "1") (pinfunction "1_1") (pintype "passive"))
      (node (ref "CHG_LED") (pin "A") (pinfunction "A_A") (pintype "passive"))
      (node (ref "D1") (pin "2") (pinfunction "GND_2") (pintype "bidirectional"))
      (node (ref "D2") (pin "2") (pinfunction "ANODE_2") (pintype "bidirectional"))
      (node (ref "PFMF.050.1") (pin "2") (pinfunction "2_2") (pintype "passive"))
      (node (ref "Q1") (pin "1") (pinfunction "G_1") (pintype "bidirectional"))
      (node (ref "R1_PWRUSB") (pin "2") (pinfunction "2_2") (pintype "passive"))
      (node (ref "U1") (pin "4") (pinfunction "VIN_4") (pintype "power_in"))
      (node (ref "VBUS") (pin "TP") (pinfunction "TP_TP") (pintype "input"))
    )
    (net (code "54") (name "VRTC") (class "Default")
      (node (ref "C10_SUPERCAP") (pin "2") (pinfunction "2_2") (pintype "passive"))
      (node (ref "C8") (pin "1") (pinfunction "1_1") (pintype "passive"))
      (node (ref "R_CAPACITOR") (pin "2") (pinfunction "2_2") (pintype "passive"))
      (node (ref "U5") (pin "14") (pinfunction "VBAT_14") (pintype "power_in"))
    )
    (net (code "55") (name "VUSB") (class "Default")
      (node (ref "J1") (pin "A4") (pinfunction "A4_A4") (pintype "bidirectional"))
      (node (ref "J1") (pin "A9") (pinfunction "A9_A9") (pintype "bidirectional"))
      (node (ref "J1") (pin "B4") (pinfunction "B4_B4") (pintype "bidirectional"))
      (node (ref "J1") (pin "B9") (pinfunction "B9_B9") (pintype "bidirectional"))
      (node (ref "PFMF.050.1") (pin "1") (pinfunction "1_1") (pintype "passive"))
    )
    (net (code "56") (name "unconnected-(IC1-NC-Pad4)") (class "Default")
      (node (ref "IC1") (pin "4") (pinfunction "NC_4") (pintype "no_connect"))
    )
    (net (code "57") (name "unconnected-(IC2-NC-Pad4)") (class "Default")
      (node (ref "IC2") (pin "4") (pinfunction "NC_4") (pintype "no_connect"))
    )
    (net (code "58") (name "unconnected-(J1-PadA8)") (class "Default")
      (node (ref "J1") (pin "A8") (pinfunction "A8_A8") (pintype "bidirectional"))
    )
    (net (code "59") (name "unconnected-(J1-PadB8)") (class "Default")
      (node (ref "J1") (pin "B8") (pinfunction "B8_B8") (pintype "bidirectional"))
    )
    (net (code "60") (name "unconnected-(J2-DAT1-PadP8)") (class "Default")
      (node (ref "J2") (pin "P8") (pinfunction "DAT1_P8") (pintype "bidirectional"))
    )
    (net (code "61") (name "unconnected-(J2-DAT2-PadP1)") (class "Default")
      (node (ref "J2") (pin "P1") (pinfunction "DAT2_P1") (pintype "bidirectional"))
    )
    (net (code "62") (name "unconnected-(J2-DETECTION_1-PadS1)") (class "Default")
      (node (ref "J2") (pin "S1") (pinfunction "DETECTION_1_S1") (pintype "bidirectional"))
    )
    (net (code "63") (name "unconnected-(J2-DETECTION_2-PadS2)") (class "Default")
      (node (ref "J2") (pin "S2") (pinfunction "DETECTION_2_S2") (pintype "bidirectional"))
    )
    (net (code "64") (name "unconnected-(J3-Pad1)") (class "Default")
      (node (ref "J3") (pin "1") (pinfunction "1_1") (pintype "bidirectional"))
    )
    (net (code "65") (name "unconnected-(J3-Pad6)") (class "Default")
      (node (ref "J3") (pin "6") (pinfunction "6_6") (pintype "bidirectional"))
    )
    (net (code "66") (name "unconnected-(J3-Pad7)") (class "Default")
      (node (ref "J3") (pin "7") (pinfunction "7_7") (pintype "bidirectional"))
    )
    (net (code "67") (name "unconnected-(U2-NC-Pad22)") (class "Default")
      (node (ref "U2") (pin "22") (pinfunction "NC_22") (pintype "no_connect"))
    )
    (net (code "68") (name "unconnected-(U4-~{ALERT}-Pad5)") (class "Default")
      (node (ref "U4") (pin "5") (pinfunction "~{ALERT}_5") (pintype "output"))
    )
  )
)
